# 3_cpu.net
KiCad netlist of a schematic drawn in Altium Designer
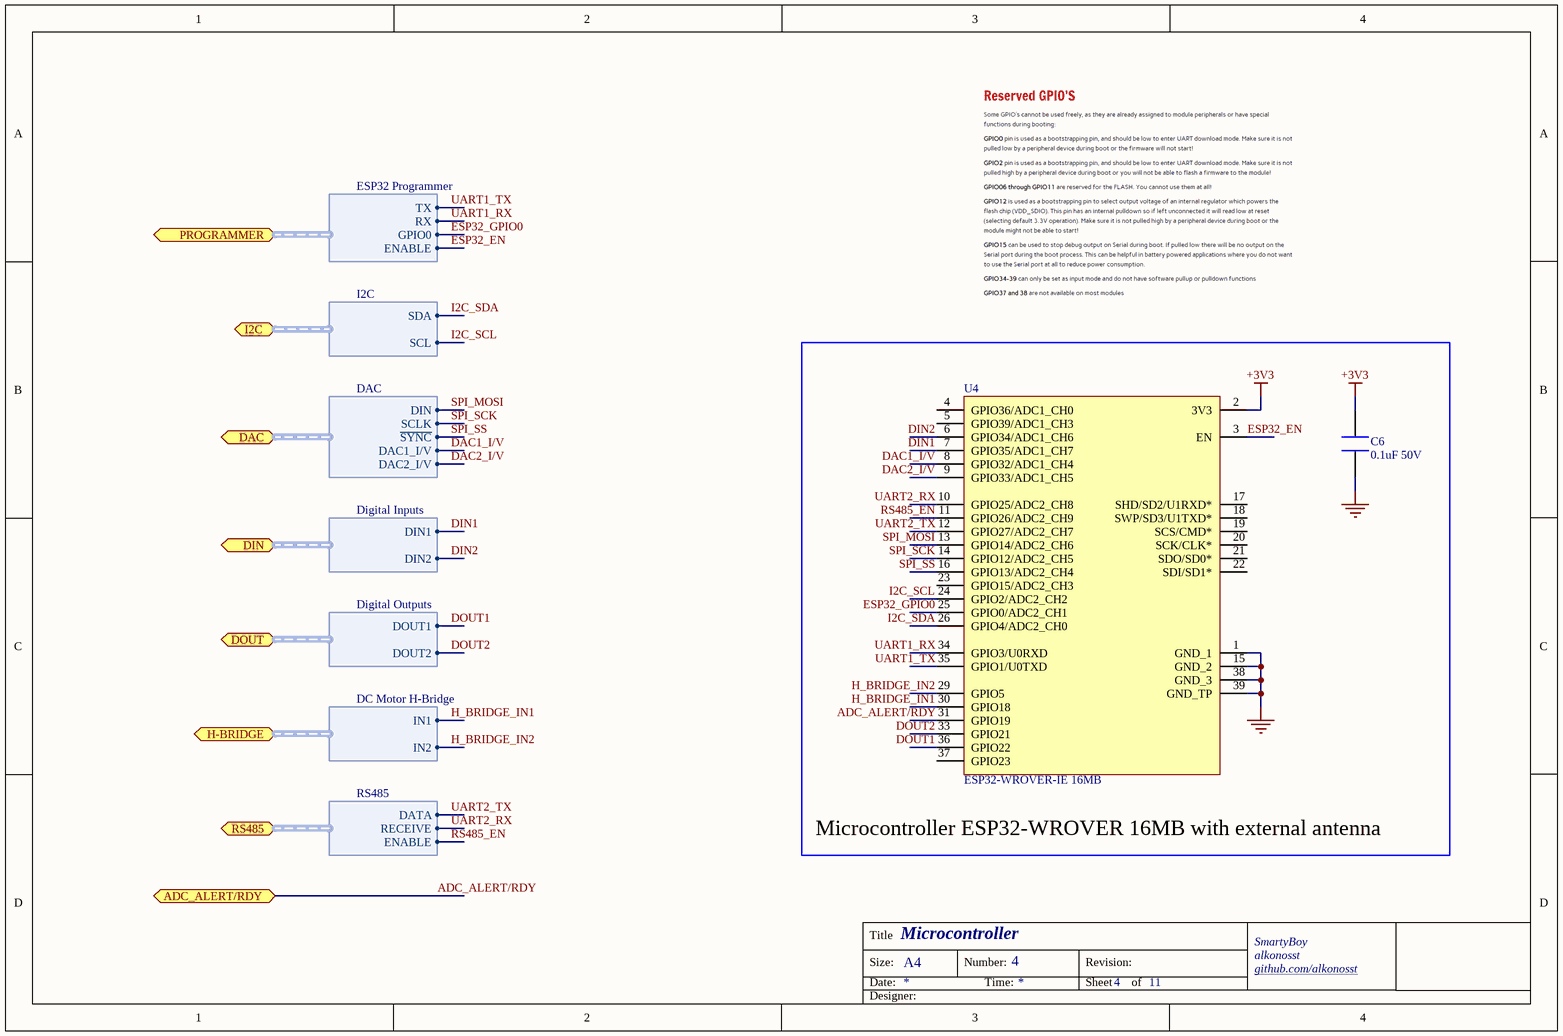
[diagram p0: 3_cpu.SchDoc]

(export (version "E")
  (design (tool "Eeschema 10.0.6"))
  (components
    (comp (ref "C6")
      (value "0.1uF 50V")
      (footprint "C0603")
      (description "X7R 100nF ±10% 50V 0603 Multilayer Ceramic Capacitors MLCC - SMD/SMT")
      (fields (field (name "LCSC PART") "C14663"))
      (libsource (lib "nombre_por_definir") (part "CC0603KRX7R9BB104"))
    )
    (comp (ref "U4")
      (value "ESP32-WROVER-IE 16MB")
      (footprint "ESP32-WROVER-IE")
      (description "RX TXRX MOD WIFI EXT IPEX SMD")
      (fields (field (name "LCSC PART") "C701352"))
      (libsource (lib "nombre_por_definir") (part "ESP32-WROVER-IE(16MB)"))
    )
  )
  (nets
    (net (code "12") (name "+3V3") (class "Default")
      (node (ref "C6") (pin "1") (pinfunction "1_1") (pintype "passive"))
      (node (ref "U4") (pin "2") (pinfunction "3V3_2") (pintype "passive"))
    )
    (net (code "13") (name "/ADC_ALERT{slash}RDY") (class "Default")
      (node (ref "U4") (pin "31") (pinfunction "GPIO19_31") (pintype "passive"))
    )
    (net (code "14") (name "/DAC1_I{slash}V") (class "Default")
      (node (ref "U4") (pin "8") (pinfunction "GPIO32/ADC1_CH4_8") (pintype "passive"))
    )
    (net (code "15") (name "/DAC2_I{slash}V") (class "Default")
      (node (ref "U4") (pin "9") (pinfunction "GPIO33/ADC1_CH5_9") (pintype "passive"))
    )
    (net (code "16") (name "/DIN1") (class "Default")
      (node (ref "U4") (pin "7") (pinfunction "GPIO35/ADC1_CH7_7") (pintype "passive"))
    )
    (net (code "17") (name "/DIN2") (class "Default")
      (node (ref "U4") (pin "6") (pinfunction "GPIO34/ADC1_CH6_6") (pintype "passive"))
    )
    (net (code "18") (name "/DOUT1") (class "Default")
      (node (ref "U4") (pin "36") (pinfunction "GPIO22_36") (pintype "passive"))
    )
    (net (code "19") (name "/DOUT2") (class "Default")
      (node (ref "U4") (pin "33") (pinfunction "GPIO21_33") (pintype "passive"))
    )
    (net (code "20") (name "/ESP32_EN") (class "Default")
      (node (ref "U4") (pin "3") (pinfunction "EN_3") (pintype "passive"))
    )
    (net (code "21") (name "/ESP32_GPIO0") (class "Default")
      (node (ref "U4") (pin "25") (pinfunction "GPIO0/ADC2_CH1_25") (pintype "passive"))
    )
    (net (code "22") (name "/H_BRIDGE_IN1") (class "Default")
      (node (ref "U4") (pin "30") (pinfunction "GPIO18_30") (pintype "passive"))
    )
    (net (code "23") (name "/H_BRIDGE_IN2") (class "Default")
      (node (ref "U4") (pin "29") (pinfunction "GPIO5_29") (pintype "passive"))
    )
    (net (code "24") (name "/I2C_SCL") (class "Default")
      (node (ref "U4") (pin "24") (pinfunction "GPIO2/ADC2_CH2_24") (pintype "passive"))
    )
    (net (code "25") (name "/I2C_SDA") (class "Default")
      (node (ref "U4") (pin "26") (pinfunction "GPIO4/ADC2_CH0_26") (pintype "passive"))
    )
    (net (code "26") (name "/RS485_EN") (class "Default")
      (node (ref "U4") (pin "11") (pinfunction "GPIO26/ADC2_CH9_11") (pintype "passive"))
    )
    (net (code "27") (name "/SPI_MOSI") (class "Default")
      (node (ref "U4") (pin "13") (pinfunction "GPIO14/ADC2_CH6_13") (pintype "passive"))
    )
    (net (code "28") (name "/SPI_SCK") (class "Default")
      (node (ref "U4") (pin "14") (pinfunction "GPIO12/ADC2_CH5_14") (pintype "passive"))
    )
    (net (code "29") (name "/SPI_SS") (class "Default")
      (node (ref "U4") (pin "16") (pinfunction "GPIO13/ADC2_CH4_16") (pintype "passive"))
    )
    (net (code "30") (name "/UART1_RX") (class "Default")
      (node (ref "U4") (pin "34") (pinfunction "GPIO3/U0RXD_34") (pintype "passive"))
    )
    (net (code "31") (name "/UART1_TX") (class "Default")
      (node (ref "U4") (pin "35") (pinfunction "GPIO1/U0TXD_35") (pintype "passive"))
    )
    (net (code "32") (name "/UART2_RX") (class "Default")
      (node (ref "U4") (pin "10") (pinfunction "GPIO25/ADC2_CH8_10") (pintype "passive"))
    )
    (net (code "33") (name "/UART2_TX") (class "Default")
      (node (ref "U4") (pin "12") (pinfunction "GPIO27/ADC2_CH7_12") (pintype "passive"))
    )
    (net (code "41") (name "GND") (class "Default")
      (node (ref "C6") (pin "2") (pinfunction "2_2") (pintype "passive"))
      (node (ref "U4") (pin "1") (pinfunction "GND_1_1") (pintype "passive"))
      (node (ref "U4") (pin "15") (pinfunction "GND_2_15") (pintype "passive"))
      (node (ref "U4") (pin "38") (pinfunction "GND_3_38") (pintype "passive"))
      (node (ref "U4") (pin "39") (pinfunction "GND_TP_39") (pintype "passive"))
    )
    (net (code "42") (name "unconnected-(U4-GPIO15{slash}ADC2_CH3-Pad23)") (class "Default")
      (node (ref "U4") (pin "23") (pinfunction "GPIO15/ADC2_CH3_23") (pintype "passive"))
    )
    (net (code "43") (name "unconnected-(U4-GPIO23-Pad37)") (class "Default")
      (node (ref "U4") (pin "37") (pinfunction "GPIO23_37") (pintype "passive"))
    )
    (net (code "44") (name "unconnected-(U4-GPIO36{slash}ADC1_CH0-Pad4)") (class "Default")
      (node (ref "U4") (pin "4") (pinfunction "GPIO36/ADC1_CH0_4") (pintype "passive"))
    )
    (net (code "45") (name "unconnected-(U4-GPIO39{slash}ADC1_CH3-Pad5)") (class "Default")
      (node (ref "U4") (pin "5") (pinfunction "GPIO39/ADC1_CH3_5") (pintype "passive"))
    )
    (net (code "46") (name "unconnected-(U4-SCK{slash}CLK*-Pad20)") (class "Default")
      (node (ref "U4") (pin "20") (pinfunction "SCK/CLK*_20") (pintype "passive"))
    )
    (net (code "47") (name "unconnected-(U4-SCS{slash}CMD*-Pad19)") (class "Default")
      (node (ref "U4") (pin "19") (pinfunction "SCS/CMD*_19") (pintype "passive"))
    )
    (net (code "48") (name "unconnected-(U4-SDI{slash}SD1*-Pad22)") (class "Default")
      (node (ref "U4") (pin "22") (pinfunction "SDI/SD1*_22") (pintype "passive"))
    )
    (net (code "49") (name "unconnected-(U4-SDO{slash}SD0*-Pad21)") (class "Default")
      (node (ref "U4") (pin "21") (pinfunction "SDO/SD0*_21") (pintype "passive"))
    )
    (net (code "50") (name "unconnected-(U4-SHD{slash}SD2{slash}U1RXD*-Pad17)") (class "Default")
      (node (ref "U4") (pin "17") (pinfunction "SHD/SD2/U1RXD*_17") (pintype "passive"))
    )
    (net (code "51") (name "unconnected-(U4-SWP{slash}SD3{slash}U1TXD*-Pad18)") (class "Default")
      (node (ref "U4") (pin "18") (pinfunction "SWP/SD3/U1TXD*_18") (pintype "passive"))
    )
  )
)
